# 2312_PIC32.net
KiCad netlist of a schematic drawn in Altium Designer
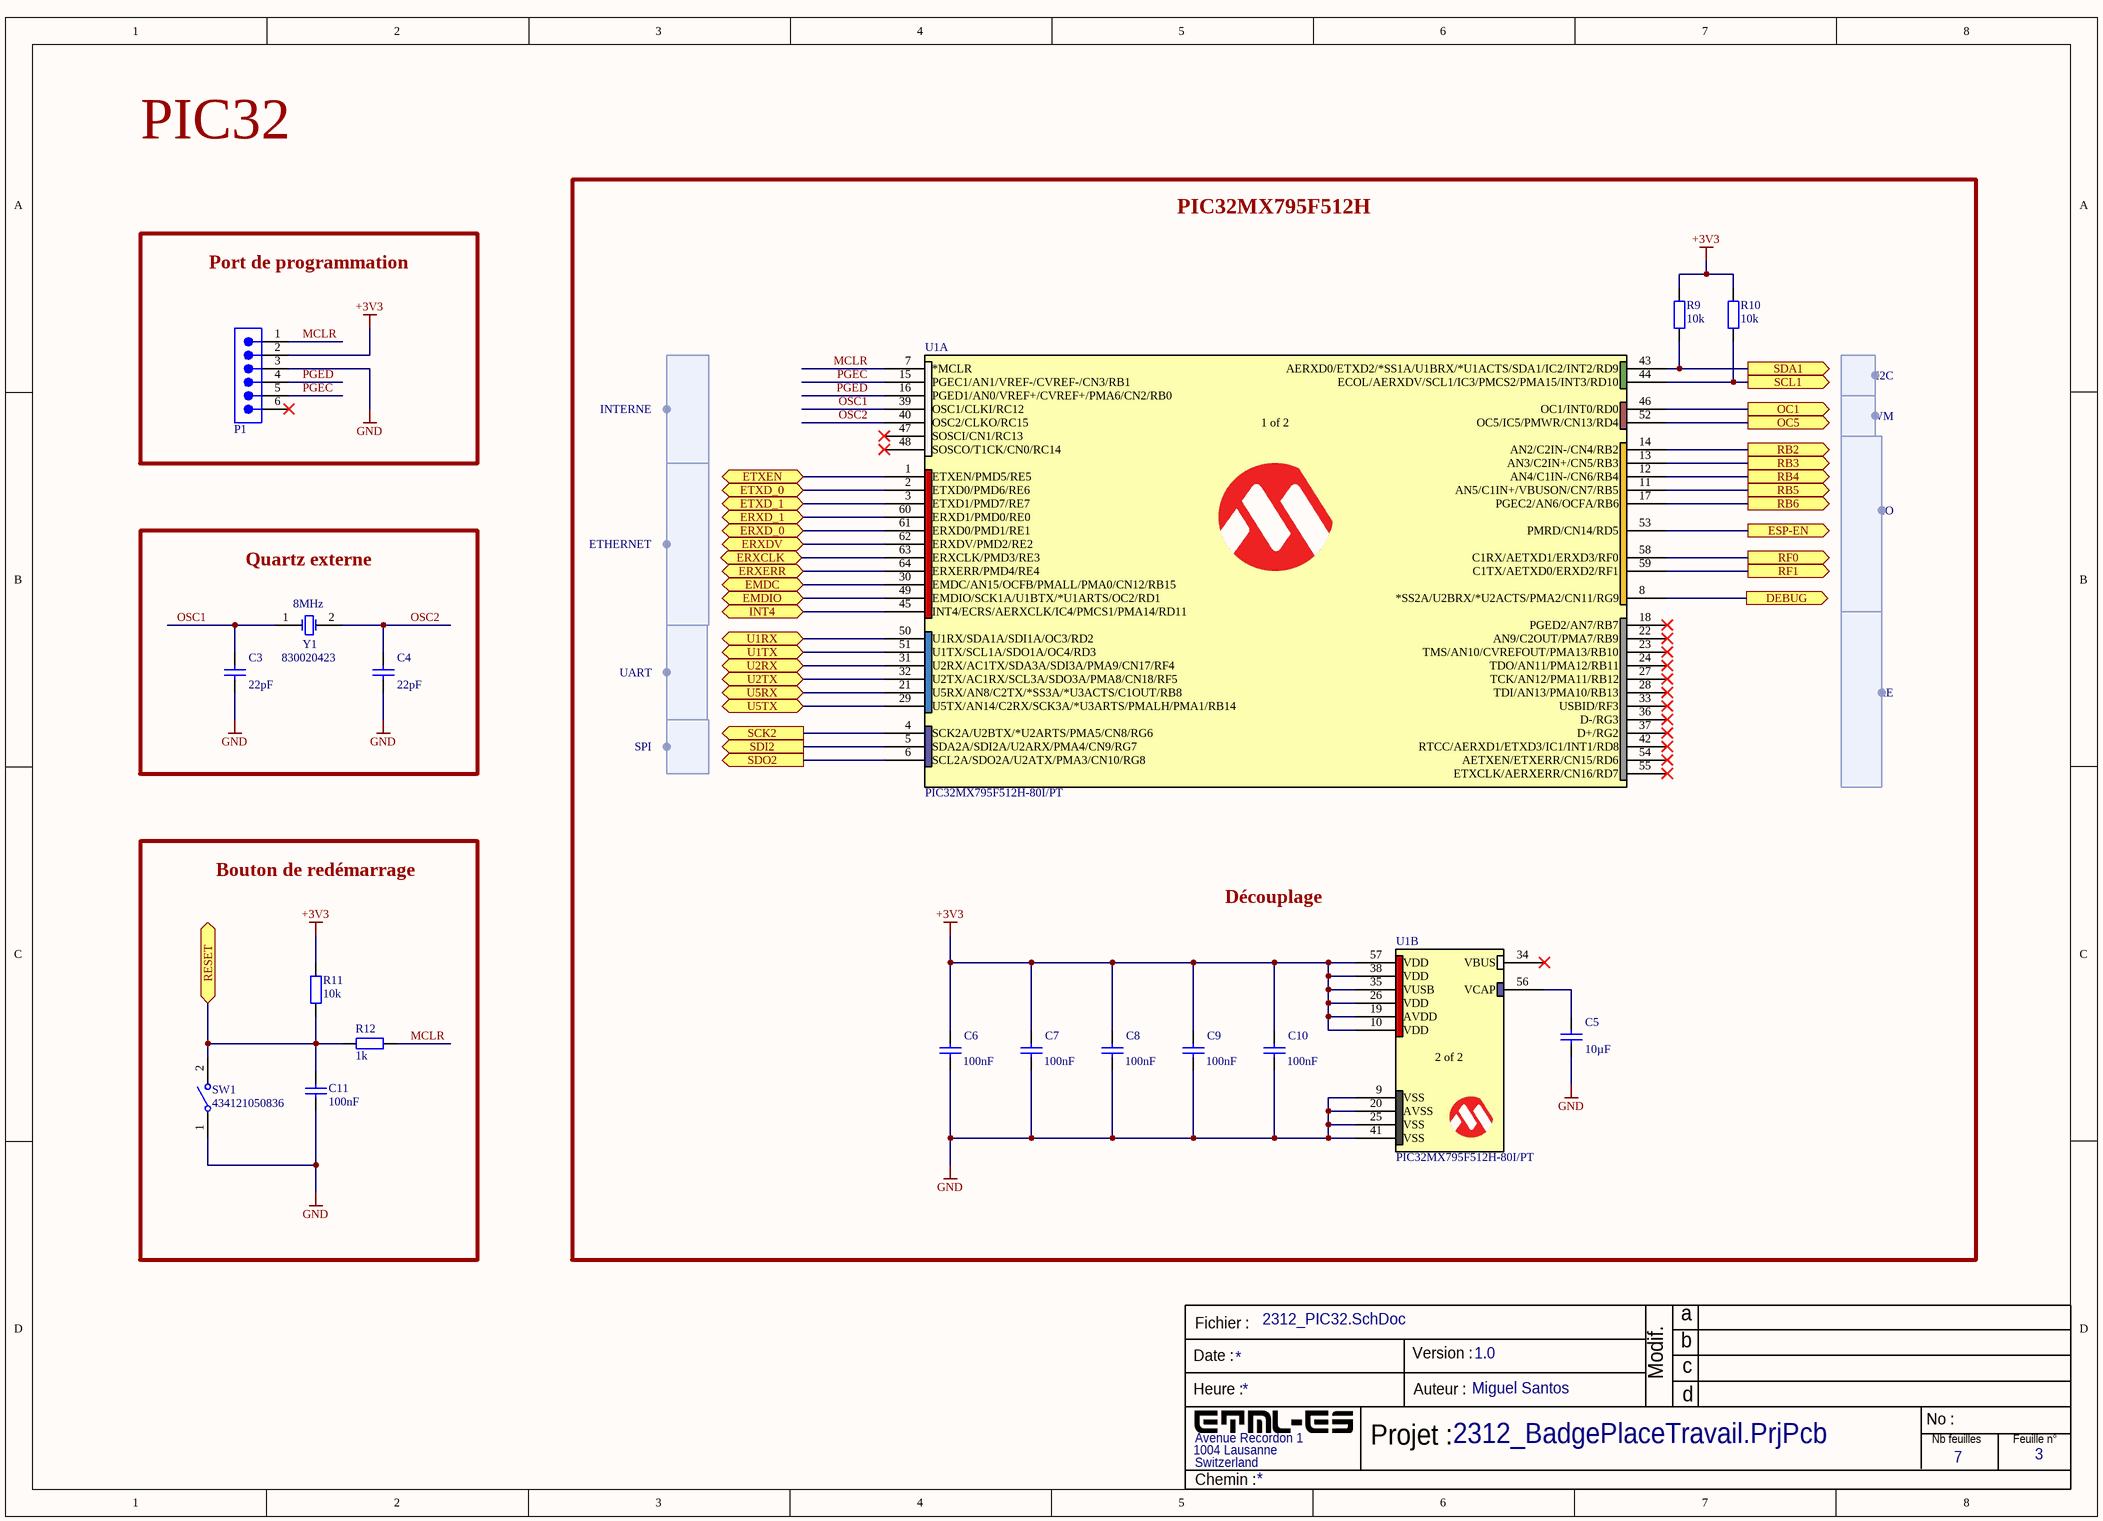
[diagram p0: 2312_PIC32.SchDoc]

(export (version "E")
  (design (tool "Eeschema 10.0.6"))
  (components
    (comp (ref "C3")
      (value "885012007002")
      (footprint "WCAP-CSGP_0805_L2W1.25H0.6_Reflow")
      (description "WCAP-CSGP Multilayer Ceramic Chip Capacitor, General Purpose, size 0805, NP0, 22pF, 10VDC")
      (fields (field (name "MANUFACTURER") "Wurth Elektronik") (field (name "CAPACITANCE") "22pF"))
      (libsource (lib "WCAP-CSGP") (part "885012007002"))
    )
    (comp (ref "C4")
      (value "885012007002")
      (footprint "WCAP-CSGP_0805_L2W1.25H0.6_Reflow")
      (description "WCAP-CSGP Multilayer Ceramic Chip Capacitor, General Purpose, size 0805, NP0, 22pF, 10VDC")
      (fields (field (name "MANUFACTURER") "Wurth Elektronik") (field (name "CAPACITANCE") "22pF"))
      (libsource (lib "WCAP-CSGP") (part "885012007002"))
    )
    (comp (ref "C5")
      (value "885012207003")
      (footprint "WCAP-CSGP_0805_L2W1.25H1.25")
      (description "WCAP-CSGP Multilayer Ceramic Chip Capacitor, General Purpose, size 0805, X7R, 10µF, 6.3VDC")
      (fields (field (name "MANUFACTURER") "Wurth Elektronik") (field (name "CAPACITANCE") "10µF"))
      (libsource (lib "WCAP-CSGP") (part "885012207003"))
    )
    (comp (ref "C6")
      (value "885012207016")
      (footprint "WCAP-CSGP_0805_L2W1.25H0.8_Reflow")
      (description "WCAP-CSGP Multilayer Ceramic Chip Capacitor, General Purpose, size 0805, X7R, 100nF, 10VDC")
      (fields (field (name "MANUFACTURER") "Wurth Elektronik") (field (name "CAPACITANCE") "100nF"))
      (libsource (lib "WCAP-CSGP") (part "885012207016"))
    )
    (comp (ref "C7")
      (value "885012207016")
      (footprint "WCAP-CSGP_0805_L2W1.25H0.8_Reflow")
      (description "WCAP-CSGP Multilayer Ceramic Chip Capacitor, General Purpose, size 0805, X7R, 100nF, 10VDC")
      (fields (field (name "MANUFACTURER") "Wurth Elektronik") (field (name "CAPACITANCE") "100nF"))
      (libsource (lib "WCAP-CSGP") (part "885012207016"))
    )
    (comp (ref "C8")
      (value "885012207016")
      (footprint "WCAP-CSGP_0805_L2W1.25H0.8_Reflow")
      (description "WCAP-CSGP Multilayer Ceramic Chip Capacitor, General Purpose, size 0805, X7R, 100nF, 10VDC")
      (fields (field (name "MANUFACTURER") "Wurth Elektronik") (field (name "CAPACITANCE") "100nF"))
      (libsource (lib "WCAP-CSGP") (part "885012207016"))
    )
    (comp (ref "C9")
      (value "885012207016")
      (footprint "WCAP-CSGP_0805_L2W1.25H0.8_Reflow")
      (description "WCAP-CSGP Multilayer Ceramic Chip Capacitor, General Purpose, size 0805, X7R, 100nF, 10VDC")
      (fields (field (name "MANUFACTURER") "Wurth Elektronik") (field (name "CAPACITANCE") "100nF"))
      (libsource (lib "WCAP-CSGP") (part "885012207016"))
    )
    (comp (ref "C10")
      (value "885012207016")
      (footprint "WCAP-CSGP_0805_L2W1.25H0.8_Reflow")
      (description "WCAP-CSGP Multilayer Ceramic Chip Capacitor, General Purpose, size 0805, X7R, 100nF, 10VDC")
      (fields (field (name "MANUFACTURER") "Wurth Elektronik") (field (name "CAPACITANCE") "100nF"))
      (libsource (lib "WCAP-CSGP") (part "885012207016"))
    )
    (comp (ref "C11")
      (value "885012207016")
      (footprint "WCAP-CSGP_0805_L2W1.25H0.8_Reflow")
      (description "WCAP-CSGP Multilayer Ceramic Chip Capacitor, General Purpose, size 0805, X7R, 100nF, 10VDC")
      (fields (field (name "MANUFACTURER") "Wurth Elektronik") (field (name "CAPACITANCE") "100nF"))
      (libsource (lib "WCAP-CSGP") (part "885012207016"))
    )
    (comp (ref "P1")
      (value "61300611121")
      (footprint "61300611121")
      (description "WR-PHD Pin Header, THT, Vertical, pitch 2.54mm, 1 Row, 6P")
      (fields (field (name "MANUFACTURER") "Wurth Elektronik"))
      (libsource (lib "WR-PHD") (part "61300611121"))
    )
    (comp (ref "R9")
      (value "RES-0805")
      (footprint "2312-RES-0805")
      (description "SMD Resistor 0805, 10kΩ")
      (fields (field (name "RESISTANCE") "10k"))
      (libsource (lib "2312-MS-0805") (part "RES-0805"))
    )
    (comp (ref "R10")
      (value "RES-0805")
      (footprint "2312-RES-0805")
      (description "SMD Resistor 0805, 10kΩ")
      (fields (field (name "RESISTANCE") "10k"))
      (libsource (lib "2312-MS-0805") (part "RES-0805"))
    )
    (comp (ref "R11")
      (value "RES-0805")
      (footprint "2312-RES-0805")
      (description "SMD Resistor 0805, 10kΩ")
      (fields (field (name "RESISTANCE") "10k"))
      (libsource (lib "2312-MS-0805") (part "RES-0805"))
    )
    (comp (ref "R12")
      (value "RES-0805")
      (footprint "2312-RES-0805")
      (description "SMD Resistor 0805, 1kΩ")
      (fields (field (name "RESISTANCE") "1k"))
      (libsource (lib "2312-MS-0805") (part "RES-0805"))
    )
    (comp (ref "SW1")
      (value "434121050836")
      (footprint "WS-TASV_L6W3.5H5_4341x10508x6")
      (description "WS-TASV SMT Tact Switch, L6 x W3.5 x H5mm, 360g, SPST-NO, 12V, 50mA")
      (fields (field (name "MANUFACTURER") "Wurth Elektronik"))
      (libsource (lib "WS-TASV") (part "434121050836"))
    )
    (comp (ref "U1")
      (value "PIC32MX795F512H-80I/PT")
      (footprint "TQFP64_10x10MC_MCH")
      (description "No Description Available")
      (libsource (lib "PIC32MX795F512H-80I_PT") (part "PIC32MX795F512H-80I/PT"))
    )
    (comp (ref "Y1")
      (value "830020423")
      (footprint "WE-XTAL_HC49/4HSMX")
      (description "WE-XTAL Quartz Crystal, SMT, HC49/4HSMX, 8MHz, +/-30ppm")
      (fields (field (name "MANUFACTURER") "Wurth Elektronik") (field (name "FREQUENCY") "8MHz"))
      (libsource (lib "WE-XTAL") (part "830020423"))
    )
  )
  (nets
    (net (code "1") (name "+3V3") (class "Default")
      (node (ref "C10") (pin "2") (pinfunction "2_2") (pintype "passive"))
      (node (ref "C6") (pin "2") (pinfunction "2_2") (pintype "passive"))
      (node (ref "C7") (pin "2") (pinfunction "2_2") (pintype "passive"))
      (node (ref "C8") (pin "2") (pinfunction "2_2") (pintype "passive"))
      (node (ref "C9") (pin "2") (pinfunction "2_2") (pintype "passive"))
      (node (ref "P1") (pin "2") (pinfunction "2_2") (pintype "passive"))
      (node (ref "R10") (pin "1") (pinfunction "1_1") (pintype "passive"))
      (node (ref "R11") (pin "1") (pinfunction "1_1") (pintype "passive"))
      (node (ref "R9") (pin "2") (pinfunction "2_2") (pintype "passive"))
      (node (ref "U1") (pin "10") (pinfunction "VDD_10") (pintype "passive"))
      (node (ref "U1") (pin "19") (pinfunction "AVDD_19") (pintype "passive"))
      (node (ref "U1") (pin "26") (pinfunction "VDD_26") (pintype "passive"))
      (node (ref "U1") (pin "35") (pinfunction "VUSB_35") (pintype "passive"))
      (node (ref "U1") (pin "38") (pinfunction "VDD_38") (pintype "passive"))
      (node (ref "U1") (pin "57") (pinfunction "VDD_57") (pintype "passive"))
    )
    (net (code "2") (name "/DEBUG") (class "Default")
      (node (ref "U1") (pin "8") (pinfunction "*SS2A/U2BRX/*U2ACTS/PMA2/CN11/RG9_8") (pintype "passive"))
    )
    (net (code "3") (name "/EMDC") (class "Default")
      (node (ref "U1") (pin "30") (pinfunction "EMDC/AN15/OCFB/PMALL/PMA0/CN12/RB15_30") (pintype "passive"))
    )
    (net (code "4") (name "/EMDIO") (class "Default")
      (node (ref "U1") (pin "49") (pinfunction "EMDIO/SCK1A/U1BTX/*U1ARTS/OC2/RD1_49") (pintype "passive"))
    )
    (net (code "5") (name "/ERXCLK") (class "Default")
      (node (ref "U1") (pin "63") (pinfunction "ERXCLK/PMD3/RE3_63") (pintype "passive"))
    )
    (net (code "6") (name "/ERXDV") (class "Default")
      (node (ref "U1") (pin "62") (pinfunction "ERXDV/PMD2/RE2_62") (pintype "passive"))
    )
    (net (code "7") (name "/ERXD_0") (class "Default")
      (node (ref "U1") (pin "61") (pinfunction "ERXD0/PMD1/RE1_61") (pintype "passive"))
    )
    (net (code "8") (name "/ERXD_1") (class "Default")
      (node (ref "U1") (pin "60") (pinfunction "ERXD1/PMD0/RE0_60") (pintype "passive"))
    )
    (net (code "9") (name "/ERXERR") (class "Default")
      (node (ref "U1") (pin "64") (pinfunction "ERXERR/PMD4/RE4_64") (pintype "passive"))
    )
    (net (code "10") (name "/ESP-EN") (class "Default")
      (node (ref "U1") (pin "53") (pinfunction "PMRD/CN14/RD5_53") (pintype "passive"))
    )
    (net (code "11") (name "/ETXD_0") (class "Default")
      (node (ref "U1") (pin "2") (pinfunction "ETXD0/PMD6/RE6_2") (pintype "passive"))
    )
    (net (code "12") (name "/ETXD_1") (class "Default")
      (node (ref "U1") (pin "3") (pinfunction "ETXD1/PMD7/RE7_3") (pintype "passive"))
    )
    (net (code "13") (name "/ETXEN") (class "Default")
      (node (ref "U1") (pin "1") (pinfunction "ETXEN/PMD5/RE5_1") (pintype "passive"))
    )
    (net (code "14") (name "/INT4") (class "Default")
      (node (ref "U1") (pin "45") (pinfunction "INT4/ECRS/AERXCLK/IC4/PMCS1/PMA14/RD11_45") (pintype "passive"))
    )
    (net (code "15") (name "/MCLR") (class "Default")
      (node (ref "P1") (pin "1") (pinfunction "1_1") (pintype "passive"))
      (node (ref "R12") (pin "2") (pinfunction "2_2") (pintype "passive"))
      (node (ref "U1") (pin "7") (pinfunction "*MCLR_7") (pintype "passive"))
    )
    (net (code "16") (name "/OC1") (class "Default")
      (node (ref "U1") (pin "46") (pinfunction "OC1/INT0/RD0_46") (pintype "passive"))
    )
    (net (code "17") (name "/OC5") (class "Default")
      (node (ref "U1") (pin "52") (pinfunction "OC5/IC5/PMWR/CN13/RD4_52") (pintype "passive"))
    )
    (net (code "18") (name "/OSC1") (class "Default")
      (node (ref "C3") (pin "2") (pinfunction "2_2") (pintype "passive"))
      (node (ref "U1") (pin "39") (pinfunction "OSC1/CLKI/RC12_39") (pintype "passive"))
      (node (ref "Y1") (pin "1") (pinfunction "OSC1_1") (pintype "passive"))
    )
    (net (code "19") (name "/OSC2") (class "Default")
      (node (ref "C4") (pin "1") (pinfunction "1_1") (pintype "passive"))
      (node (ref "U1") (pin "40") (pinfunction "OSC2/CLKO/RC15_40") (pintype "passive"))
      (node (ref "Y1") (pin "2") (pinfunction "OSC2_2") (pintype "passive"))
    )
    (net (code "20") (name "/PGEC") (class "Default")
      (node (ref "P1") (pin "5") (pinfunction "5_5") (pintype "passive"))
      (node (ref "U1") (pin "15") (pinfunction "PGEC1/AN1/VREF-/CVREF-/CN3/RB1_15") (pintype "passive"))
    )
    (net (code "21") (name "/PGED") (class "Default")
      (node (ref "P1") (pin "4") (pinfunction "4_4") (pintype "passive"))
      (node (ref "U1") (pin "16") (pinfunction "PGED1/AN0/VREF+/CVREF+/PMA6/CN2/RB0_16") (pintype "passive"))
    )
    (net (code "22") (name "/RB2") (class "Default")
      (node (ref "U1") (pin "14") (pinfunction "AN2/C2IN-/CN4/RB2_14") (pintype "passive"))
    )
    (net (code "23") (name "/RB3") (class "Default")
      (node (ref "U1") (pin "13") (pinfunction "AN3/C2IN+/CN5/RB3_13") (pintype "passive"))
    )
    (net (code "24") (name "/RB4") (class "Default")
      (node (ref "U1") (pin "12") (pinfunction "AN4/C1IN-/CN6/RB4_12") (pintype "passive"))
    )
    (net (code "25") (name "/RB5") (class "Default")
      (node (ref "U1") (pin "11") (pinfunction "AN5/C1IN+/VBUSON/CN7/RB5_11") (pintype "passive"))
    )
    (net (code "26") (name "/RB6") (class "Default")
      (node (ref "U1") (pin "17") (pinfunction "PGEC2/AN6/OCFA/RB6_17") (pintype "passive"))
    )
    (net (code "27") (name "/RESET") (class "Default")
      (node (ref "C11") (pin "1") (pinfunction "1_1") (pintype "passive"))
      (node (ref "R11") (pin "2") (pinfunction "2_2") (pintype "passive"))
      (node (ref "R12") (pin "1") (pinfunction "1_1") (pintype "passive"))
      (node (ref "SW1") (pin "2") (pinfunction "2_2") (pintype "passive"))
    )
    (net (code "28") (name "/RF0") (class "Default")
      (node (ref "U1") (pin "58") (pinfunction "C1RX/AETXD1/ERXD3/RF0_58") (pintype "passive"))
    )
    (net (code "29") (name "/RF1") (class "Default")
      (node (ref "U1") (pin "59") (pinfunction "C1TX/AETXD0/ERXD2/RF1_59") (pintype "passive"))
    )
    (net (code "30") (name "/SCK2") (class "Default")
      (node (ref "U1") (pin "4") (pinfunction "SCK2A/U2BTX/*U2ARTS/PMA5/CN8/RG6_4") (pintype "passive"))
    )
    (net (code "31") (name "/SCL1") (class "Default")
      (node (ref "R10") (pin "2") (pinfunction "2_2") (pintype "passive"))
      (node (ref "U1") (pin "44") (pinfunction "ECOL/AERXDV/SCL1/IC3/PMCS2/PMA15/INT3/RD10_44") (pintype "passive"))
    )
    (net (code "32") (name "/SDA1") (class "Default")
      (node (ref "R9") (pin "1") (pinfunction "1_1") (pintype "passive"))
      (node (ref "U1") (pin "43") (pinfunction "AERXD0/ETXD2/*SS1A/U1BRX/*U1ACTS/SDA1/IC2/INT2/RD9_43") (pintype "passive"))
    )
    (net (code "33") (name "/SDI2") (class "Default")
      (node (ref "U1") (pin "5") (pinfunction "SDA2A/SDI2A/U2ARX/PMA4/CN9/RG7_5") (pintype "passive"))
    )
    (net (code "34") (name "/SDO2") (class "Default")
      (node (ref "U1") (pin "6") (pinfunction "SCL2A/SDO2A/U2ATX/PMA3/CN10/RG8_6") (pintype "passive"))
    )
    (net (code "35") (name "/U1RX") (class "Default")
      (node (ref "U1") (pin "50") (pinfunction "U1RX/SDA1A/SDI1A/OC3/RD2_50") (pintype "passive"))
    )
    (net (code "36") (name "/U1TX") (class "Default")
      (node (ref "U1") (pin "51") (pinfunction "U1TX/SCL1A/SDO1A/OC4/RD3_51") (pintype "passive"))
    )
    (net (code "37") (name "/U2RX") (class "Default")
      (node (ref "U1") (pin "31") (pinfunction "U2RX/AC1TX/SDA3A/SDI3A/PMA9/CN17/RF4_31") (pintype "passive"))
    )
    (net (code "38") (name "/U2TX") (class "Default")
      (node (ref "U1") (pin "32") (pinfunction "U2TX/AC1RX/SCL3A/SDO3A/PMA8/CN18/RF5_32") (pintype "passive"))
    )
    (net (code "39") (name "/U5RX") (class "Default")
      (node (ref "U1") (pin "21") (pinfunction "U5RX/AN8/C2TX/*SS3A/*U3ACTS/C1OUT/RB8_21") (pintype "passive"))
    )
    (net (code "40") (name "/U5TX") (class "Default")
      (node (ref "U1") (pin "29") (pinfunction "U5TX/AN14/C2RX/SCK3A/*U3ARTS/PMALH/PMA1/RB14_29") (pintype "passive"))
    )
    (net (code "41") (name "GND") (class "Default")
      (node (ref "C10") (pin "1") (pinfunction "1_1") (pintype "passive"))
      (node (ref "C11") (pin "2") (pinfunction "2_2") (pintype "passive"))
      (node (ref "C3") (pin "1") (pinfunction "1_1") (pintype "passive"))
      (node (ref "C4") (pin "2") (pinfunction "2_2") (pintype "passive"))
      (node (ref "C5") (pin "1") (pinfunction "1_1") (pintype "passive"))
      (node (ref "C6") (pin "1") (pinfunction "1_1") (pintype "passive"))
      (node (ref "C7") (pin "1") (pinfunction "1_1") (pintype "passive"))
      (node (ref "C8") (pin "1") (pinfunction "1_1") (pintype "passive"))
      (node (ref "C9") (pin "1") (pinfunction "1_1") (pintype "passive"))
      (node (ref "P1") (pin "3") (pinfunction "3_3") (pintype "passive"))
      (node (ref "SW1") (pin "1") (pinfunction "1_1") (pintype "passive"))
      (node (ref "U1") (pin "20") (pinfunction "AVSS_20") (pintype "passive"))
      (node (ref "U1") (pin "25") (pinfunction "VSS_25") (pintype "passive"))
      (node (ref "U1") (pin "41") (pinfunction "VSS_41") (pintype "passive"))
      (node (ref "U1") (pin "9") (pinfunction "VSS_9") (pintype "passive"))
    )
    (net (code "42") (name "Net-(U1B-VCAP)") (class "Default")
      (node (ref "C5") (pin "2") (pinfunction "2_2") (pintype "passive"))
      (node (ref "U1") (pin "56") (pinfunction "VCAP_56") (pintype "passive"))
    )
    (net (code "43") (name "unconnected-(P1-Pad6)") (class "Default")
      (node (ref "P1") (pin "6") (pinfunction "6_6") (pintype "passive+no_connect"))
    )
    (net (code "44") (name "unconnected-(U1A-AETXEN{slash}ETXERR{slash}CN15{slash}RD6-Pad54)") (class "Default")
      (node (ref "U1") (pin "54") (pinfunction "AETXEN/ETXERR/CN15/RD6_54") (pintype "passive+no_connect"))
    )
    (net (code "45") (name "unconnected-(U1A-AN9{slash}C2OUT{slash}PMA7{slash}RB9-Pad22)") (class "Default")
      (node (ref "U1") (pin "22") (pinfunction "AN9/C2OUT/PMA7/RB9_22") (pintype "passive+no_connect"))
    )
    (net (code "46") (name "unconnected-(U1A-D+{slash}RG2-Pad37)") (class "Default")
      (node (ref "U1") (pin "37") (pinfunction "D+/RG2_37") (pintype "passive+no_connect"))
    )
    (net (code "47") (name "unconnected-(U1A-D-{slash}RG3-Pad36)") (class "Default")
      (node (ref "U1") (pin "36") (pinfunction "D-/RG3_36") (pintype "passive+no_connect"))
    )
    (net (code "48") (name "unconnected-(U1A-ETXCLK{slash}AERXERR{slash}CN16{slash}RD7-Pad55)") (class "Default")
      (node (ref "U1") (pin "55") (pinfunction "ETXCLK/AERXERR/CN16/RD7_55") (pintype "passive+no_connect"))
    )
    (net (code "49") (name "unconnected-(U1A-PGED2{slash}AN7{slash}RB7-Pad18)") (class "Default")
      (node (ref "U1") (pin "18") (pinfunction "PGED2/AN7/RB7_18") (pintype "passive+no_connect"))
    )
    (net (code "50") (name "unconnected-(U1A-RTCC{slash}AERXD1{slash}ETXD3{slash}IC1{slash}INT1{slash}RD8-Pad42)") (class "Default")
      (node (ref "U1") (pin "42") (pinfunction "RTCC/AERXD1/ETXD3/IC1/INT1/RD8_42") (pintype "passive+no_connect"))
    )
    (net (code "51") (name "unconnected-(U1A-SOSCI{slash}CN1{slash}RC13-Pad47)") (class "Default")
      (node (ref "U1") (pin "47") (pinfunction "SOSCI/CN1/RC13_47") (pintype "passive+no_connect"))
    )
    (net (code "52") (name "unconnected-(U1A-SOSCO{slash}T1CK{slash}CN0{slash}RC14-Pad48)") (class "Default")
      (node (ref "U1") (pin "48") (pinfunction "SOSCO/T1CK/CN0/RC14_48") (pintype "passive+no_connect"))
    )
    (net (code "53") (name "unconnected-(U1A-TCK{slash}AN12{slash}PMA11{slash}RB12-Pad27)") (class "Default")
      (node (ref "U1") (pin "27") (pinfunction "TCK/AN12/PMA11/RB12_27") (pintype "passive+no_connect"))
    )
    (net (code "54") (name "unconnected-(U1A-TDI{slash}AN13{slash}PMA10{slash}RB13-Pad28)") (class "Default")
      (node (ref "U1") (pin "28") (pinfunction "TDI/AN13/PMA10/RB13_28") (pintype "passive+no_connect"))
    )
    (net (code "55") (name "unconnected-(U1A-TDO{slash}AN11{slash}PMA12{slash}RB11-Pad24)") (class "Default")
      (node (ref "U1") (pin "24") (pinfunction "TDO/AN11/PMA12/RB11_24") (pintype "passive+no_connect"))
    )
    (net (code "56") (name "unconnected-(U1A-TMS{slash}AN10{slash}CVREFOUT{slash}PMA13{slash}RB10-Pad23)") (class "Default")
      (node (ref "U1") (pin "23") (pinfunction "TMS/AN10/CVREFOUT/PMA13/RB10_23") (pintype "passive+no_connect"))
    )
    (net (code "57") (name "unconnected-(U1A-USBID{slash}RF3-Pad33)") (class "Default")
      (node (ref "U1") (pin "33") (pinfunction "USBID/RF3_33") (pintype "passive+no_connect"))
    )
    (net (code "58") (name "unconnected-(U1B-VBUS-Pad34)") (class "Default")
      (node (ref "U1") (pin "34") (pinfunction "VBUS_34") (pintype "passive+no_connect"))
    )
  )
)
